# Xcore10.net
KiCad netlist of a schematic drawn in Altium Designer
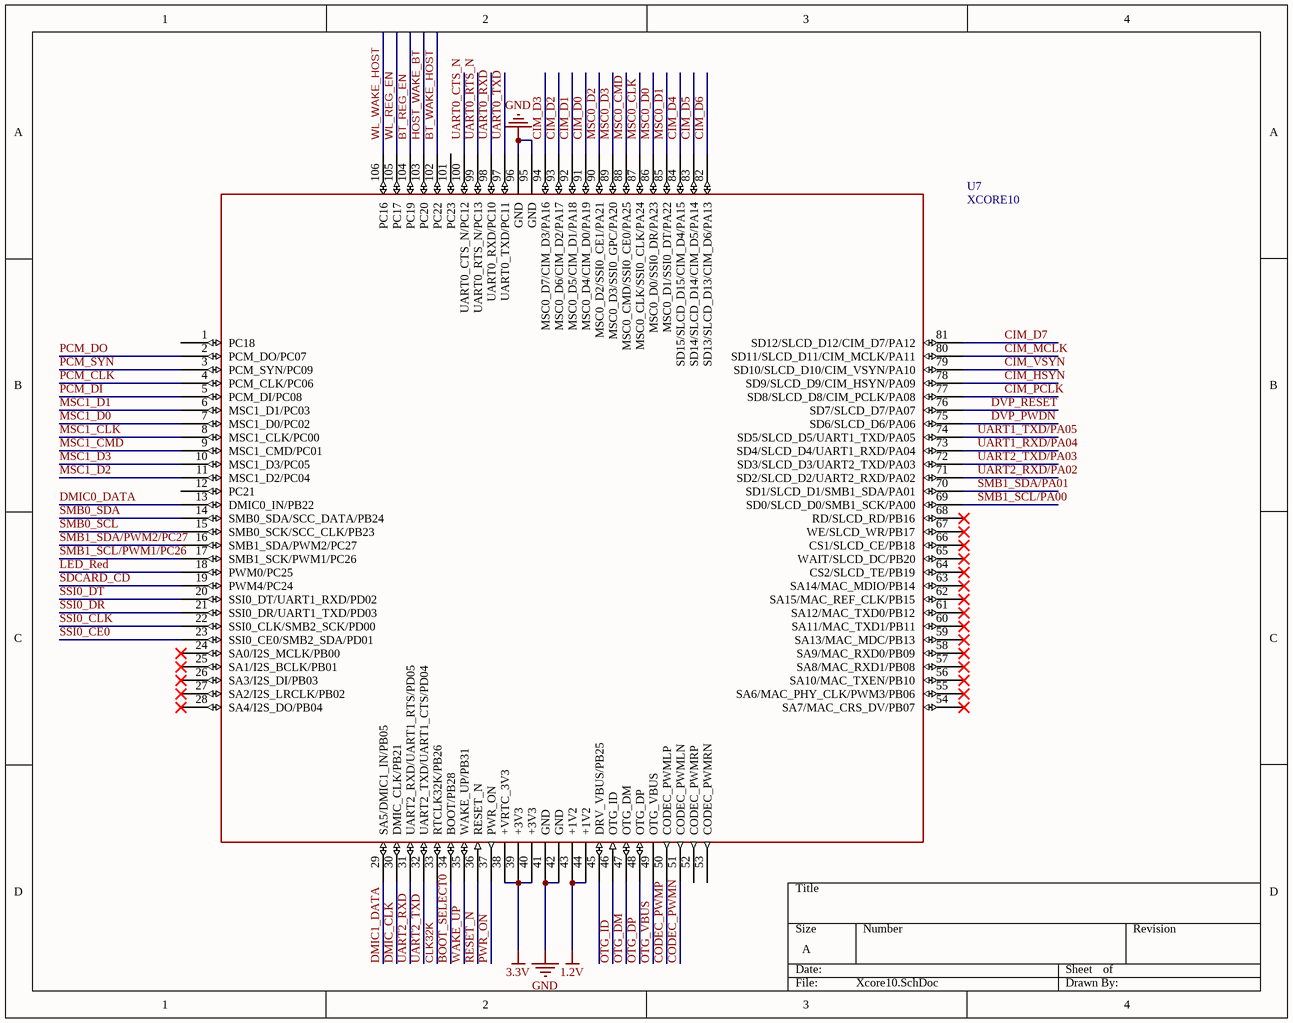
[diagram p0: Xcore10.SchDoc]

(export (version "E")
  (design (tool "Eeschema 10.0.6"))
  (components
    (comp (ref "U7")
      (value "XCORE10")
      (footprint "CORE-32*26-1.0")
      (libsource (lib "Ingenic") (part "XCORE10"))
    )
  )
  (nets
    (net (code "1") (name "/BOOT_SELECT0") (class "Default")
      (node (ref "U7") (pin "34") (pinfunction "BOOT/PB28_34") (pintype "bidirectional"))
    )
    (net (code "2") (name "/BT_REG_EN") (class "Default")
      (node (ref "U7") (pin "104") (pinfunction "PC19_104") (pintype "bidirectional"))
    )
    (net (code "3") (name "/BT_WAKE_HOST") (class "Default")
      (node (ref "U7") (pin "102") (pinfunction "PC22_102") (pintype "bidirectional"))
    )
    (net (code "4") (name "/CIM_D0") (class "Default")
      (node (ref "U7") (pin "91") (pinfunction "MSC0_D4/CIM_D0/PA19_91") (pintype "bidirectional"))
    )
    (net (code "5") (name "/CIM_D1") (class "Default")
      (node (ref "U7") (pin "92") (pinfunction "MSC0_D5/CIM_D1/PA18_92") (pintype "bidirectional"))
    )
    (net (code "6") (name "/CIM_D2") (class "Default")
      (node (ref "U7") (pin "93") (pinfunction "MSC0_D6/CIM_D2/PA17_93") (pintype "bidirectional"))
    )
    (net (code "7") (name "/CIM_D3") (class "Default")
      (node (ref "U7") (pin "94") (pinfunction "MSC0_D7/CIM_D3/PA16_94") (pintype "bidirectional"))
    )
    (net (code "8") (name "/CIM_D4") (class "Default")
      (node (ref "U7") (pin "84") (pinfunction "SD15/SLCD_D15/CIM_D4/PA15_84") (pintype "bidirectional"))
    )
    (net (code "9") (name "/CIM_D5") (class "Default")
      (node (ref "U7") (pin "83") (pinfunction "SD14/SLCD_D14/CIM_D5/PA14_83") (pintype "bidirectional"))
    )
    (net (code "10") (name "/CIM_D6") (class "Default")
      (node (ref "U7") (pin "82") (pinfunction "SD13/SLCD_D13/CIM_D6/PA13_82") (pintype "bidirectional"))
    )
    (net (code "11") (name "/CIM_D7") (class "Default")
      (node (ref "U7") (pin "81") (pinfunction "SD12/SLCD_D12/CIM_D7/PA12_81") (pintype "bidirectional"))
    )
    (net (code "12") (name "/CIM_HSYN") (class "Default")
      (node (ref "U7") (pin "78") (pinfunction "SD9/SLCD_D9/CIM_HSYN/PA09_78") (pintype "bidirectional"))
    )
    (net (code "13") (name "/CIM_MCLK") (class "Default")
      (node (ref "U7") (pin "80") (pinfunction "SD11/SLCD_D11/CIM_MCLK/PA11_80") (pintype "bidirectional"))
    )
    (net (code "14") (name "/CIM_PCLK") (class "Default")
      (node (ref "U7") (pin "77") (pinfunction "SD8/SLCD_D8/CIM_PCLK/PA08_77") (pintype "bidirectional"))
    )
    (net (code "15") (name "/CIM_VSYN") (class "Default")
      (node (ref "U7") (pin "79") (pinfunction "SD10/SLCD_D10/CIM_VSYN/PA10_79") (pintype "bidirectional"))
    )
    (net (code "16") (name "/CLK32K") (class "Default")
      (node (ref "U7") (pin "33") (pinfunction "RTCLK32K/PB26_33") (pintype "bidirectional"))
    )
    (net (code "17") (name "/CODEC_PWMN") (class "Default")
      (node (ref "U7") (pin "51") (pinfunction "CODEC_PWMLN_51") (pintype "output"))
    )
    (net (code "18") (name "/CODEC_PWMP") (class "Default")
      (node (ref "U7") (pin "50") (pinfunction "CODEC_PWMLP_50") (pintype "output"))
    )
    (net (code "19") (name "/DMIC0_DATA") (class "Default")
      (node (ref "U7") (pin "13") (pinfunction "DMIC0_IN/PB22_13") (pintype "bidirectional"))
    )
    (net (code "20") (name "/DMIC1_DATA") (class "Default")
      (node (ref "U7") (pin "29") (pinfunction "SA5/DMIC1_IN/PB05_29") (pintype "bidirectional"))
    )
    (net (code "21") (name "/DMIC_CLK") (class "Default")
      (node (ref "U7") (pin "30") (pinfunction "DMIC_CLK/PB21_30") (pintype "bidirectional"))
    )
    (net (code "22") (name "/DVP_PWDN") (class "Default")
      (node (ref "U7") (pin "75") (pinfunction "SD6/SLCD_D6/PA06_75") (pintype "bidirectional"))
    )
    (net (code "23") (name "/DVP_RESET") (class "Default")
      (node (ref "U7") (pin "76") (pinfunction "SD7/SLCD_D7/PA07_76") (pintype "bidirectional"))
    )
    (net (code "24") (name "/HOST_WAKE_BT") (class "Default")
      (node (ref "U7") (pin "103") (pinfunction "PC20_103") (pintype "bidirectional"))
    )
    (net (code "25") (name "/LED_Red") (class "Default")
      (node (ref "U7") (pin "18") (pinfunction "PWM0/PC25_18") (pintype "bidirectional"))
    )
    (net (code "26") (name "/MSC0_CLK") (class "Default")
      (node (ref "U7") (pin "87") (pinfunction "MSC0_CLK/SSI0_CLK/PA24_87") (pintype "bidirectional"))
    )
    (net (code "27") (name "/MSC0_CMD") (class "Default")
      (node (ref "U7") (pin "88") (pinfunction "MSC0_CMD/SSI0_CE0/PA25_88") (pintype "bidirectional"))
    )
    (net (code "28") (name "/MSC0_D0") (class "Default")
      (node (ref "U7") (pin "86") (pinfunction "MSC0_D0/SSI0_DR/PA23_86") (pintype "bidirectional"))
    )
    (net (code "29") (name "/MSC0_D1") (class "Default")
      (node (ref "U7") (pin "85") (pinfunction "MSC0_D1/SSI0_DT/PA22_85") (pintype "bidirectional"))
    )
    (net (code "30") (name "/MSC0_D2") (class "Default")
      (node (ref "U7") (pin "90") (pinfunction "MSC0_D2/SSI0_CE1/PA21_90") (pintype "bidirectional"))
    )
    (net (code "31") (name "/MSC0_D3") (class "Default")
      (node (ref "U7") (pin "89") (pinfunction "MSC0_D3/SSI0_GPC/PA20_89") (pintype "bidirectional"))
    )
    (net (code "32") (name "/MSC1_CLK") (class "Default")
      (node (ref "U7") (pin "8") (pinfunction "MSC1_CLK/PC00_8") (pintype "bidirectional"))
    )
    (net (code "33") (name "/MSC1_CMD") (class "Default")
      (node (ref "U7") (pin "9") (pinfunction "MSC1_CMD/PC01_9") (pintype "bidirectional"))
    )
    (net (code "34") (name "/MSC1_D0") (class "Default")
      (node (ref "U7") (pin "7") (pinfunction "MSC1_D0/PC02_7") (pintype "bidirectional"))
    )
    (net (code "35") (name "/MSC1_D1") (class "Default")
      (node (ref "U7") (pin "6") (pinfunction "MSC1_D1/PC03_6") (pintype "bidirectional"))
    )
    (net (code "36") (name "/MSC1_D2") (class "Default")
      (node (ref "U7") (pin "11") (pinfunction "MSC1_D2/PC04_11") (pintype "bidirectional"))
    )
    (net (code "37") (name "/MSC1_D3") (class "Default")
      (node (ref "U7") (pin "10") (pinfunction "MSC1_D3/PC05_10") (pintype "bidirectional"))
    )
    (net (code "38") (name "/OTG_DM") (class "Default")
      (node (ref "U7") (pin "47") (pinfunction "OTG_DM_47") (pintype "bidirectional"))
    )
    (net (code "39") (name "/OTG_DP") (class "Default")
      (node (ref "U7") (pin "48") (pinfunction "OTG_DP_48") (pintype "bidirectional"))
    )
    (net (code "40") (name "/OTG_ID") (class "Default")
      (node (ref "U7") (pin "46") (pinfunction "OTG_ID_46") (pintype "input"))
    )
    (net (code "41") (name "/OTG_VBUS") (class "Default")
      (node (ref "U7") (pin "49") (pinfunction "OTG_VBUS_49") (pintype "power_in"))
    )
    (net (code "42") (name "/PCM_CLK") (class "Default")
      (node (ref "U7") (pin "4") (pinfunction "PCM_CLK/PC06_4") (pintype "bidirectional"))
    )
    (net (code "43") (name "/PCM_DI") (class "Default")
      (node (ref "U7") (pin "5") (pinfunction "PCM_DI/PC08_5") (pintype "bidirectional"))
    )
    (net (code "44") (name "/PCM_DO") (class "Default")
      (node (ref "U7") (pin "2") (pinfunction "PCM_DO/PC07_2") (pintype "bidirectional"))
    )
    (net (code "45") (name "/PCM_SYN") (class "Default")
      (node (ref "U7") (pin "3") (pinfunction "PCM_SYN/PC09_3") (pintype "bidirectional"))
    )
    (net (code "46") (name "/PWR_ON") (class "Default")
      (node (ref "U7") (pin "37") (pinfunction "PWR_ON_37") (pintype "output"))
    )
    (net (code "47") (name "/RESET_N") (class "Default")
      (node (ref "U7") (pin "36") (pinfunction "RESET_N_36") (pintype "input"))
    )
    (net (code "48") (name "/SDCARD_CD") (class "Default")
      (node (ref "U7") (pin "19") (pinfunction "PWM4/PC24_19") (pintype "bidirectional"))
    )
    (net (code "49") (name "/SMB0_SCL") (class "Default")
      (node (ref "U7") (pin "15") (pinfunction "SMB0_SCK/SCC_CLK/PB23_15") (pintype "bidirectional"))
    )
    (net (code "50") (name "/SMB0_SDA") (class "Default")
      (node (ref "U7") (pin "14") (pinfunction "SMB0_SDA/SCC_DATA/PB24_14") (pintype "bidirectional"))
    )
    (net (code "51") (name "/SMB1_SCL{slash}PA00") (class "Default")
      (node (ref "U7") (pin "69") (pinfunction "SD0/SLCD_D0/SMB1_SCK/PA00_69") (pintype "bidirectional"))
    )
    (net (code "52") (name "/SMB1_SCL{slash}PWM1{slash}PC26") (class "Default")
      (node (ref "U7") (pin "17") (pinfunction "SMB1_SCK/PWM1/PC26_17") (pintype "bidirectional"))
    )
    (net (code "53") (name "/SMB1_SDA{slash}PA01") (class "Default")
      (node (ref "U7") (pin "70") (pinfunction "SD1/SLCD_D1/SMB1_SDA/PA01_70") (pintype "bidirectional"))
    )
    (net (code "54") (name "/SMB1_SDA{slash}PWM2{slash}PC27") (class "Default")
      (node (ref "U7") (pin "16") (pinfunction "SMB1_SDA/PWM2/PC27_16") (pintype "bidirectional"))
    )
    (net (code "55") (name "/SSI0_CE0") (class "Default")
      (node (ref "U7") (pin "23") (pinfunction "SSI0_CE0/SMB2_SDA/PD01_23") (pintype "bidirectional"))
    )
    (net (code "56") (name "/SSI0_CLK") (class "Default")
      (node (ref "U7") (pin "22") (pinfunction "SSI0_CLK/SMB2_SCK/PD00_22") (pintype "bidirectional"))
    )
    (net (code "57") (name "/SSI0_DR") (class "Default")
      (node (ref "U7") (pin "21") (pinfunction "SSI0_DR/UART1_TXD/PD03_21") (pintype "bidirectional"))
    )
    (net (code "58") (name "/SSI0_DT") (class "Default")
      (node (ref "U7") (pin "20") (pinfunction "SSI0_DT/UART1_RXD/PD02_20") (pintype "bidirectional"))
    )
    (net (code "59") (name "/UART0_CTS_N") (class "Default")
      (node (ref "U7") (pin "100") (pinfunction "UART0_CTS_N/PC12_100") (pintype "bidirectional"))
    )
    (net (code "60") (name "/UART0_RTS_N") (class "Default")
      (node (ref "U7") (pin "99") (pinfunction "UART0_RTS_N/PC13_99") (pintype "bidirectional"))
    )
    (net (code "61") (name "/UART0_RXD") (class "Default")
      (node (ref "U7") (pin "98") (pinfunction "UART0_RXD/PC10_98") (pintype "bidirectional"))
    )
    (net (code "62") (name "/UART0_TXD") (class "Default")
      (node (ref "U7") (pin "97") (pinfunction "UART0_TXD/PC11_97") (pintype "bidirectional"))
    )
    (net (code "63") (name "/UART1_RXD{slash}PA04") (class "Default")
      (node (ref "U7") (pin "73") (pinfunction "SD4/SLCD_D4/UART1_RXD/PA04_73") (pintype "bidirectional"))
    )
    (net (code "64") (name "/UART1_TXD{slash}PA05") (class "Default")
      (node (ref "U7") (pin "74") (pinfunction "SD5/SLCD_D5/UART1_TXD/PA05_74") (pintype "bidirectional"))
    )
    (net (code "65") (name "/UART2_RXD") (class "Default")
      (node (ref "U7") (pin "31") (pinfunction "UART2_RXD/UART1_RTS/PD05_31") (pintype "bidirectional"))
    )
    (net (code "66") (name "/UART2_RXD{slash}PA02") (class "Default")
      (node (ref "U7") (pin "71") (pinfunction "SD2/SLCD_D2/UART2_RXD/PA02_71") (pintype "bidirectional"))
    )
    (net (code "67") (name "/UART2_TXD") (class "Default")
      (node (ref "U7") (pin "32") (pinfunction "UART2_TXD/UART1_CTS/PD04_32") (pintype "bidirectional"))
    )
    (net (code "68") (name "/UART2_TXD{slash}PA03") (class "Default")
      (node (ref "U7") (pin "72") (pinfunction "SD3/SLCD_D3/UART2_TXD/PA03_72") (pintype "bidirectional"))
    )
    (net (code "69") (name "/WAKE_UP") (class "Default")
      (node (ref "U7") (pin "35") (pinfunction "WAKE_UP/PB31_35") (pintype "bidirectional"))
    )
    (net (code "70") (name "/WL_REG_EN") (class "Default")
      (node (ref "U7") (pin "105") (pinfunction "PC17_105") (pintype "bidirectional"))
    )
    (net (code "71") (name "/WL_WAKE_HOST") (class "Default")
      (node (ref "U7") (pin "106") (pinfunction "PC16_106") (pintype "bidirectional"))
    )
    (net (code "72") (name "1.2V") (class "Default")
      (node (ref "U7") (pin "43") (pinfunction "+1V2_43") (pintype "power_in"))
      (node (ref "U7") (pin "44") (pinfunction "+1V2_44") (pintype "power_in"))
    )
    (net (code "73") (name "3.3V") (class "Default")
      (node (ref "U7") (pin "38") (pinfunction "+VRTC_3V3_38") (pintype "power_in"))
      (node (ref "U7") (pin "39") (pinfunction "+3V3_39") (pintype "power_in"))
      (node (ref "U7") (pin "40") (pinfunction "+3V3_40") (pintype "power_in"))
    )
    (net (code "74") (name "GND") (class "Default")
      (node (ref "U7") (pin "41") (pinfunction "GND_41") (pintype "power_in"))
      (node (ref "U7") (pin "42") (pinfunction "GND_42") (pintype "power_in"))
      (node (ref "U7") (pin "95") (pinfunction "GND_95") (pintype "power_in"))
      (node (ref "U7") (pin "96") (pinfunction "GND_96") (pintype "power_in"))
    )
    (net (code "75") (name "unconnected-(U7-CODEC_PWMRN-Pad53)") (class "Default")
      (node (ref "U7") (pin "53") (pinfunction "CODEC_PWMRN_53") (pintype "output"))
    )
    (net (code "76") (name "unconnected-(U7-CODEC_PWMRP-Pad52)") (class "Default")
      (node (ref "U7") (pin "52") (pinfunction "CODEC_PWMRP_52") (pintype "output"))
    )
    (net (code "77") (name "unconnected-(U7-CS1{slash}SLCD_CE{slash}PB18-Pad66)") (class "Default")
      (node (ref "U7") (pin "66") (pinfunction "CS1/SLCD_CE/PB18_66") (pintype "bidirectional+no_connect"))
    )
    (net (code "78") (name "unconnected-(U7-CS2{slash}SLCD_TE{slash}PB19-Pad64)") (class "Default")
      (node (ref "U7") (pin "64") (pinfunction "CS2/SLCD_TE/PB19_64") (pintype "bidirectional+no_connect"))
    )
    (net (code "79") (name "unconnected-(U7-DRV_VBUS{slash}PB25-Pad45)") (class "Default")
      (node (ref "U7") (pin "45") (pinfunction "DRV_VBUS/PB25_45") (pintype "bidirectional"))
    )
    (net (code "80") (name "unconnected-(U7-PC18-Pad1)") (class "Default")
      (node (ref "U7") (pin "1") (pinfunction "PC18_1") (pintype "bidirectional"))
    )
    (net (code "81") (name "unconnected-(U7-PC21-Pad12)") (class "Default")
      (node (ref "U7") (pin "12") (pinfunction "PC21_12") (pintype "bidirectional"))
    )
    (net (code "82") (name "unconnected-(U7-PC23-Pad101)") (class "Default")
      (node (ref "U7") (pin "101") (pinfunction "PC23_101") (pintype "bidirectional"))
    )
    (net (code "83") (name "unconnected-(U7-RD{slash}SLCD_RD{slash}PB16-Pad68)") (class "Default")
      (node (ref "U7") (pin "68") (pinfunction "RD/SLCD_RD/PB16_68") (pintype "bidirectional+no_connect"))
    )
    (net (code "84") (name "unconnected-(U7-SA0{slash}I2S_MCLK{slash}PB00-Pad24)") (class "Default")
      (node (ref "U7") (pin "24") (pinfunction "SA0/I2S_MCLK/PB00_24") (pintype "bidirectional+no_connect"))
    )
    (net (code "85") (name "unconnected-(U7-SA1{slash}I2S_BCLK{slash}PB01-Pad25)") (class "Default")
      (node (ref "U7") (pin "25") (pinfunction "SA1/I2S_BCLK/PB01_25") (pintype "bidirectional+no_connect"))
    )
    (net (code "86") (name "unconnected-(U7-SA2{slash}I2S_LRCLK{slash}PB02-Pad27)") (class "Default")
      (node (ref "U7") (pin "27") (pinfunction "SA2/I2S_LRCLK/PB02_27") (pintype "bidirectional+no_connect"))
    )
    (net (code "87") (name "unconnected-(U7-SA3{slash}I2S_DI{slash}PB03-Pad26)") (class "Default")
      (node (ref "U7") (pin "26") (pinfunction "SA3/I2S_DI/PB03_26") (pintype "bidirectional+no_connect"))
    )
    (net (code "88") (name "unconnected-(U7-SA4{slash}I2S_DO{slash}PB04-Pad28)") (class "Default")
      (node (ref "U7") (pin "28") (pinfunction "SA4/I2S_DO/PB04_28") (pintype "bidirectional+no_connect"))
    )
    (net (code "89") (name "unconnected-(U7-SA6{slash}MAC_PHY_CLK{slash}PWM3{slash}PB06-Pad55)") (class "Default")
      (node (ref "U7") (pin "55") (pinfunction "SA6/MAC_PHY_CLK/PWM3/PB06_55") (pintype "bidirectional+no_connect"))
    )
    (net (code "90") (name "unconnected-(U7-SA7{slash}MAC_CRS_DV{slash}PB07-Pad54)") (class "Default")
      (node (ref "U7") (pin "54") (pinfunction "SA7/MAC_CRS_DV/PB07_54") (pintype "bidirectional+no_connect"))
    )
    (net (code "91") (name "unconnected-(U7-SA8{slash}MAC_RXD1{slash}PB08-Pad57)") (class "Default")
      (node (ref "U7") (pin "57") (pinfunction "SA8/MAC_RXD1/PB08_57") (pintype "bidirectional+no_connect"))
    )
    (net (code "92") (name "unconnected-(U7-SA9{slash}MAC_RXD0{slash}PB09-Pad58)") (class "Default")
      (node (ref "U7") (pin "58") (pinfunction "SA9/MAC_RXD0/PB09_58") (pintype "bidirectional+no_connect"))
    )
    (net (code "93") (name "unconnected-(U7-SA10{slash}MAC_TXEN{slash}PB10-Pad56)") (class "Default")
      (node (ref "U7") (pin "56") (pinfunction "SA10/MAC_TXEN/PB10_56") (pintype "bidirectional+no_connect"))
    )
    (net (code "94") (name "unconnected-(U7-SA11{slash}MAC_TXD1{slash}PB11-Pad60)") (class "Default")
      (node (ref "U7") (pin "60") (pinfunction "SA11/MAC_TXD1/PB11_60") (pintype "bidirectional+no_connect"))
    )
    (net (code "95") (name "unconnected-(U7-SA12{slash}MAC_TXD0{slash}PB12-Pad61)") (class "Default")
      (node (ref "U7") (pin "61") (pinfunction "SA12/MAC_TXD0/PB12_61") (pintype "bidirectional+no_connect"))
    )
    (net (code "96") (name "unconnected-(U7-SA13{slash}MAC_MDC{slash}PB13-Pad59)") (class "Default")
      (node (ref "U7") (pin "59") (pinfunction "SA13/MAC_MDC/PB13_59") (pintype "bidirectional+no_connect"))
    )
    (net (code "97") (name "unconnected-(U7-SA14{slash}MAC_MDIO{slash}PB14-Pad63)") (class "Default")
      (node (ref "U7") (pin "63") (pinfunction "SA14/MAC_MDIO/PB14_63") (pintype "bidirectional+no_connect"))
    )
    (net (code "98") (name "unconnected-(U7-SA15{slash}MAC_REF_CLK{slash}PB15-Pad62)") (class "Default")
      (node (ref "U7") (pin "62") (pinfunction "SA15/MAC_REF_CLK/PB15_62") (pintype "bidirectional+no_connect"))
    )
    (net (code "99") (name "unconnected-(U7-WAIT{slash}SLCD_DC{slash}PB20-Pad65)") (class "Default")
      (node (ref "U7") (pin "65") (pinfunction "WAIT/SLCD_DC/PB20_65") (pintype "bidirectional+no_connect"))
    )
    (net (code "100") (name "unconnected-(U7-WE{slash}SLCD_WR{slash}PB17-Pad67)") (class "Default")
      (node (ref "U7") (pin "67") (pinfunction "WE/SLCD_WR/PB17_67") (pintype "bidirectional+no_connect"))
    )
  )
)
